# Gagabiro_supply_acdc_converter.net
KiCad netlist of a schematic drawn in Altium Designer
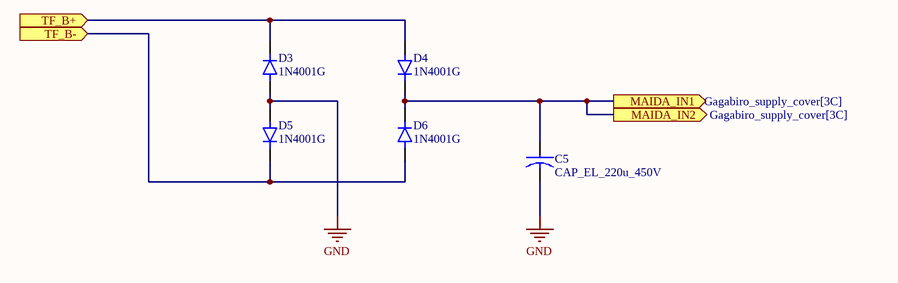
[diagram p0: Gagabiro_supply_acdc_converter.SchDoc]

(export (version "E")
  (design (tool "Eeschema 10.0.6"))
  (components
    (comp (ref "C5")
      (value "CAP_EL_220u_450V")
      (footprint "CAPPRD500W50D630H1120_stand_25x50")
      (description "220F 16V Aluminum Electrolytic Capacitors Radial, Can 1000 Hrs @ 105C")
      (fields (field (name "MP") "EEU-HD1C221B") (field (name "MF") "Panasonic"))
      (libsource (lib "Persephone_Integrated_Library") (part "CAP_EL_220u_450V"))
    )
    (comp (ref "D3")
      (value "1N4001G")
      (footprint "DIOAD1036W78L470D235")
      (description "1A, 50V, Standard Recovery Rectifier")
      (fields (field (name "MF") "Taiwan Semiconductor"))
      (libsource (lib "Persephone_Integrated_Library") (part "1N4001G"))
    )
    (comp (ref "D4")
      (value "1N4001G")
      (footprint "DIOAD1036W78L470D235")
      (description "1A, 50V, Standard Recovery Rectifier")
      (fields (field (name "MF") "Taiwan Semiconductor"))
      (libsource (lib "Persephone_Integrated_Library") (part "1N4001G"))
    )
    (comp (ref "D5")
      (value "1N4001G")
      (footprint "DIOAD1036W78L470D235")
      (description "1A, 50V, Standard Recovery Rectifier")
      (fields (field (name "MF") "Taiwan Semiconductor"))
      (libsource (lib "Persephone_Integrated_Library") (part "1N4001G"))
    )
    (comp (ref "D6")
      (value "1N4001G")
      (footprint "DIOAD1036W78L470D235")
      (description "1A, 50V, Standard Recovery Rectifier")
      (fields (field (name "MF") "Taiwan Semiconductor"))
      (libsource (lib "Persephone_Integrated_Library") (part "1N4001G"))
    )
  )
  (nets
    (net (code "1") (name "/MAIDA_IN1") (class "Default")
      (node (ref "C5") (pin "P") (pinfunction "P_P") (pintype "passive"))
      (node (ref "D4") (pin "C") (pinfunction "K_C") (pintype "passive"))
      (node (ref "D6") (pin "C") (pinfunction "K_C") (pintype "passive"))
    )
    (net (code "2") (name "/TF_B+") (class "Default")
      (node (ref "D3") (pin "C") (pinfunction "K_C") (pintype "passive"))
      (node (ref "D4") (pin "A") (pinfunction "A_A") (pintype "passive"))
    )
    (net (code "3") (name "/TF_B-") (class "Default")
      (node (ref "D5") (pin "C") (pinfunction "K_C") (pintype "passive"))
      (node (ref "D6") (pin "A") (pinfunction "A_A") (pintype "passive"))
    )
    (net (code "4") (name "GND") (class "Default")
      (node (ref "C5") (pin "N") (pinfunction "N_N") (pintype "passive"))
      (node (ref "D3") (pin "A") (pinfunction "A_A") (pintype "passive"))
      (node (ref "D5") (pin "A") (pinfunction "A_A") (pintype "passive"))
    )
  )
)
